# Yay_n_Ders_2.net
KiCad netlist of a schematic drawn in EAGLE
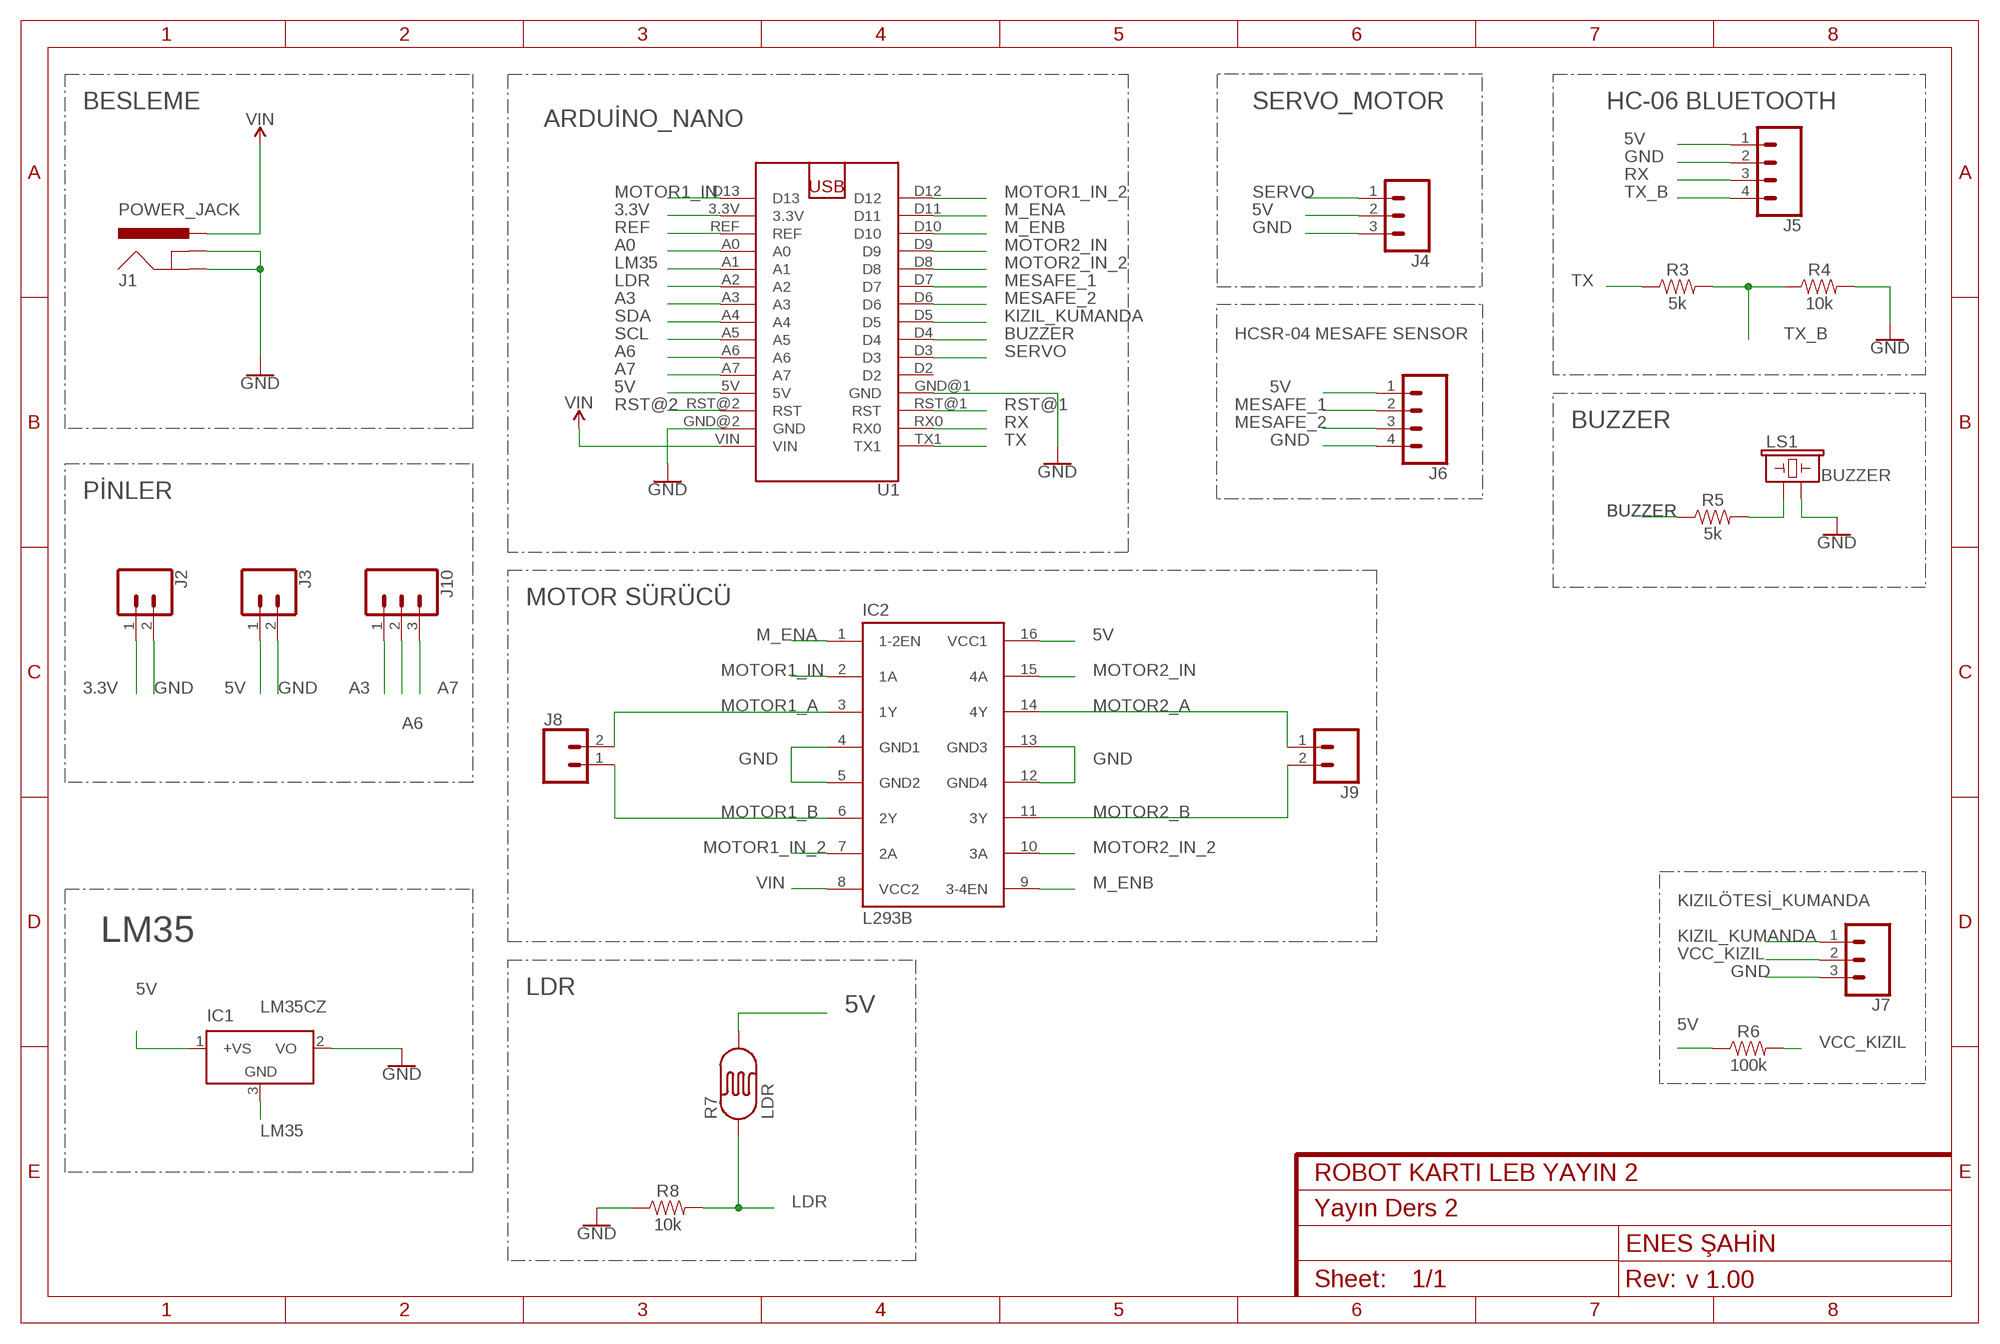
[diagram p0: schematic, sheet 1]

(export (version "E")
  (design (tool "Eeschema 10.0.6"))
  (components
    (comp (ref "IC1")
      (value "LM35CZ")
      (footprint "eagle-import:TO92")
      (libsource (lib "eagle-import") (part "LM35CZ"))
    )
    (comp (ref "IC2")
      (value "L293B")
      (footprint "eagle-import:DIL16")
      (fields (field (name "MPN") "L293D"))
      (libsource (lib "eagle-import") (part "L293D"))
    )
    (comp (ref "J1")
      (value "POWER_JACK")
      (footprint "eagle-import:POWER_JACK_PTH")
      (libsource (lib "eagle-import") (part "POWER_JACK"))
    )
    (comp (ref "J2")
      (value "CONN_02")
      (footprint "eagle-import:1X02")
      (libsource (lib "eagle-import") (part "CONN_02"))
    )
    (comp (ref "J3")
      (value "CONN_02")
      (footprint "eagle-import:1X02")
      (libsource (lib "eagle-import") (part "CONN_02"))
    )
    (comp (ref "J4")
      (value "CONN_03")
      (footprint "eagle-import:1X03")
      (libsource (lib "eagle-import") (part "CONN_03"))
    )
    (comp (ref "J5")
      (value "CONN_04")
      (footprint "eagle-import:1X04")
      (libsource (lib "eagle-import") (part "CONN_04"))
    )
    (comp (ref "J6")
      (value "CONN_04")
      (footprint "eagle-import:1X04")
      (libsource (lib "eagle-import") (part "CONN_04"))
    )
    (comp (ref "J7")
      (value "CONN_03")
      (footprint "eagle-import:1X03")
      (libsource (lib "eagle-import") (part "CONN_03"))
    )
    (comp (ref "J8")
      (value "CONN_02")
      (footprint "eagle-import:1X02")
      (libsource (lib "eagle-import") (part "CONN_02"))
    )
    (comp (ref "J9")
      (value "CONN_02")
      (footprint "eagle-import:1X02")
      (libsource (lib "eagle-import") (part "CONN_02"))
    )
    (comp (ref "J10")
      (value "CONN_03")
      (footprint "eagle-import:1X03")
      (libsource (lib "eagle-import") (part "CONN_03"))
    )
    (comp (ref "LS1")
      (value "BUZZER")
      (footprint "eagle-import:BUZZER-12MM")
      (libsource (lib "eagle-import") (part "BUZZER-PTH"))
    )
    (comp (ref "R3")
      (value "5k")
      (footprint "eagle-import:AXIAL-0.3")
      (libsource (lib "eagle-import") (part "SparkFun-Resistors_532_1KOHM-HORIZ-1/4W-1%"))
    )
    (comp (ref "R4")
      (value "10k")
      (footprint "eagle-import:AXIAL-0.3")
      (libsource (lib "eagle-import") (part "SparkFun-Resistors_532_1KOHM-HORIZ-1/4W-1%"))
    )
    (comp (ref "R5")
      (value "5k")
      (footprint "eagle-import:AXIAL-0.3")
      (libsource (lib "eagle-import") (part "SparkFun-Resistors_532_1KOHM-HORIZ-1/4W-1%"))
    )
    (comp (ref "R6")
      (value "100k")
      (footprint "eagle-import:AXIAL-0.3")
      (libsource (lib "eagle-import") (part "1KOHM-HORIZ-1/4W-1%"))
    )
    (comp (ref "R7")
      (value "LDR")
      (footprint "eagle-import:PHOTOCELL")
      (libsource (lib "eagle-import") (part "PHOTOCELLPTH"))
    )
    (comp (ref "R8")
      (value "10k")
      (footprint "eagle-import:AXIAL-0.3")
      (libsource (lib "eagle-import") (part "1KOHM-HORIZ-1/4W-1%"))
    )
    (comp (ref "U1")
      (value "ARDUINO_NANO")
      (footprint "eagle-import:ARDUINO_NANO")
      (libsource (lib "eagle-import") (part "ARDUINO_NANO"))
    )
  )
  (nets
    (net (code "1") (name "/3.3V") (class "Default")
      (node (ref "J2") (pin "1") (pinfunction "1_1") (pintype "passive"))
      (node (ref "U1") (pin "3.3V") (pinfunction "3.3V_3.3V") (pintype "bidirectional"))
    )
    (net (code "2") (name "/5V") (class "Default")
      (node (ref "IC1") (pin "1") (pinfunction "+VS_1") (pintype "input"))
      (node (ref "IC2") (pin "16") (pinfunction "VCC1_16") (pintype "power_in"))
      (node (ref "J3") (pin "1") (pinfunction "1_1") (pintype "passive"))
      (node (ref "J4") (pin "2") (pinfunction "2_2") (pintype "passive"))
      (node (ref "J5") (pin "1") (pinfunction "1_1") (pintype "passive"))
      (node (ref "J6") (pin "1") (pinfunction "1_1") (pintype "passive"))
      (node (ref "R6") (pin "P$1") (pinfunction "1_P$1") (pintype "passive"))
      (node (ref "R7") (pin "2") (pinfunction "P$2_2") (pintype "bidirectional"))
      (node (ref "U1") (pin "5V") (pinfunction "5V_5V") (pintype "bidirectional"))
    )
    (net (code "3") (name "/A0") (class "Default")
      (node (ref "U1") (pin "A0") (pinfunction "A0_A0") (pintype "bidirectional"))
    )
    (net (code "4") (name "/A3") (class "Default")
      (node (ref "J10") (pin "1") (pinfunction "1_1") (pintype "passive"))
      (node (ref "U1") (pin "A3") (pinfunction "A3_A3") (pintype "bidirectional"))
    )
    (net (code "5") (name "/A6") (class "Default")
      (node (ref "J10") (pin "2") (pinfunction "2_2") (pintype "passive"))
      (node (ref "U1") (pin "A6") (pinfunction "A6_A6") (pintype "bidirectional"))
    )
    (net (code "6") (name "/A7") (class "Default")
      (node (ref "J10") (pin "3") (pinfunction "3_3") (pintype "passive"))
      (node (ref "U1") (pin "A7") (pinfunction "A7_A7") (pintype "bidirectional"))
    )
    (net (code "7") (name "/BUZZER") (class "Default")
      (node (ref "R5") (pin "P$1") (pinfunction "1_P$1") (pintype "passive"))
      (node (ref "U1") (pin "D4") (pinfunction "D4_D4") (pintype "bidirectional"))
    )
    (net (code "8") (name "/KIZIL_KUMANDA") (class "Default")
      (node (ref "J7") (pin "1") (pinfunction "1_1") (pintype "passive"))
      (node (ref "U1") (pin "D5") (pinfunction "D5_D5") (pintype "bidirectional"))
    )
    (net (code "9") (name "/LDR") (class "Default")
      (node (ref "R7") (pin "1") (pinfunction "P$1_1") (pintype "bidirectional"))
      (node (ref "R8") (pin "P$2") (pinfunction "2_P$2") (pintype "passive"))
      (node (ref "U1") (pin "A2") (pinfunction "A2_A2") (pintype "bidirectional"))
    )
    (net (code "10") (name "/LM35") (class "Default")
      (node (ref "IC1") (pin "3") (pinfunction "GND_3") (pintype "power_in"))
      (node (ref "U1") (pin "A1") (pinfunction "A1_A1") (pintype "bidirectional"))
    )
    (net (code "11") (name "/MESAFE_1") (class "Default")
      (node (ref "J6") (pin "2") (pinfunction "2_2") (pintype "passive"))
      (node (ref "U1") (pin "D7") (pinfunction "D7_D7") (pintype "bidirectional"))
    )
    (net (code "12") (name "/MESAFE_2") (class "Default")
      (node (ref "J6") (pin "3") (pinfunction "3_3") (pintype "passive"))
      (node (ref "U1") (pin "D6") (pinfunction "D6_D6") (pintype "bidirectional"))
    )
    (net (code "13") (name "/MOTOR1_A") (class "Default")
      (node (ref "IC2") (pin "3") (pinfunction "1Y_3") (pintype "output"))
      (node (ref "J8") (pin "2") (pinfunction "2_2") (pintype "passive"))
    )
    (net (code "14") (name "/MOTOR1_B") (class "Default")
      (node (ref "IC2") (pin "6") (pinfunction "2Y_6") (pintype "output"))
      (node (ref "J8") (pin "1") (pinfunction "1_1") (pintype "passive"))
    )
    (net (code "15") (name "/MOTOR1_IN") (class "Default")
      (node (ref "IC2") (pin "2") (pinfunction "1A_2") (pintype "input"))
      (node (ref "U1") (pin "D13") (pinfunction "D13_D13") (pintype "bidirectional"))
    )
    (net (code "16") (name "/MOTOR1_IN_2") (class "Default")
      (node (ref "IC2") (pin "7") (pinfunction "2A_7") (pintype "input"))
      (node (ref "U1") (pin "D12") (pinfunction "D12_D12") (pintype "bidirectional"))
    )
    (net (code "17") (name "/MOTOR2_A") (class "Default")
      (node (ref "IC2") (pin "14") (pinfunction "4Y_14") (pintype "output"))
      (node (ref "J9") (pin "1") (pinfunction "1_1") (pintype "passive"))
    )
    (net (code "18") (name "/MOTOR2_B") (class "Default")
      (node (ref "IC2") (pin "11") (pinfunction "3Y_11") (pintype "output"))
      (node (ref "J9") (pin "2") (pinfunction "2_2") (pintype "passive"))
    )
    (net (code "19") (name "/MOTOR2_IN") (class "Default")
      (node (ref "IC2") (pin "15") (pinfunction "4A_15") (pintype "input"))
      (node (ref "U1") (pin "D9") (pinfunction "D9_D9") (pintype "bidirectional"))
    )
    (net (code "20") (name "/MOTOR2_IN_2") (class "Default")
      (node (ref "IC2") (pin "10") (pinfunction "3A_10") (pintype "input"))
      (node (ref "U1") (pin "D8") (pinfunction "D8_D8") (pintype "bidirectional"))
    )
    (net (code "21") (name "/M_ENA") (class "Default")
      (node (ref "IC2") (pin "1") (pinfunction "1-2EN_1") (pintype "input"))
      (node (ref "U1") (pin "D11") (pinfunction "D11_D11") (pintype "bidirectional"))
    )
    (net (code "22") (name "/M_ENB") (class "Default")
      (node (ref "IC2") (pin "9") (pinfunction "3-4EN_9") (pintype "input"))
      (node (ref "U1") (pin "D10") (pinfunction "D10_D10") (pintype "bidirectional"))
    )
    (net (code "23") (name "/REF") (class "Default")
      (node (ref "U1") (pin "REF") (pinfunction "REF_REF") (pintype "bidirectional"))
    )
    (net (code "24") (name "/RST@1") (class "Default")
      (node (ref "U1") (pin "RST@1") (pinfunction "RST_RST@1") (pintype "bidirectional"))
    )
    (net (code "25") (name "/RST@2") (class "Default")
      (node (ref "U1") (pin "RST@2") (pinfunction "RST_RST@2") (pintype "bidirectional"))
    )
    (net (code "26") (name "/RX") (class "Default")
      (node (ref "J5") (pin "3") (pinfunction "3_3") (pintype "passive"))
      (node (ref "U1") (pin "RX0") (pinfunction "RX0_RX0") (pintype "bidirectional"))
    )
    (net (code "27") (name "/SCL") (class "Default")
      (node (ref "U1") (pin "A5") (pinfunction "A5_A5") (pintype "bidirectional"))
    )
    (net (code "28") (name "/SDA") (class "Default")
      (node (ref "U1") (pin "A4") (pinfunction "A4_A4") (pintype "bidirectional"))
    )
    (net (code "29") (name "/SERVO") (class "Default")
      (node (ref "J4") (pin "1") (pinfunction "1_1") (pintype "passive"))
      (node (ref "U1") (pin "D3") (pinfunction "D3_D3") (pintype "bidirectional"))
    )
    (net (code "30") (name "/TX") (class "Default")
      (node (ref "R3") (pin "P$1") (pinfunction "1_P$1") (pintype "passive"))
      (node (ref "U1") (pin "TX1") (pinfunction "TX1_TX1") (pintype "bidirectional"))
    )
    (net (code "31") (name "/TX_B") (class "Default")
      (node (ref "J5") (pin "4") (pinfunction "4_4") (pintype "passive"))
      (node (ref "R3") (pin "P$2") (pinfunction "2_P$2") (pintype "passive"))
      (node (ref "R4") (pin "P$1") (pinfunction "1_P$1") (pintype "passive"))
    )
    (net (code "32") (name "/VCC_KIZIL") (class "Default")
      (node (ref "J7") (pin "2") (pinfunction "2_2") (pintype "passive"))
      (node (ref "R6") (pin "P$2") (pinfunction "2_P$2") (pintype "passive"))
    )
    (net (code "33") (name "GND") (class "Default")
      (node (ref "IC1") (pin "2") (pinfunction "VO_2") (pintype "input"))
      (node (ref "IC2") (pin "12") (pinfunction "GND4_12") (pintype "power_in"))
      (node (ref "IC2") (pin "13") (pinfunction "GND3_13") (pintype "power_in"))
      (node (ref "IC2") (pin "4") (pinfunction "GND1_4") (pintype "power_in"))
      (node (ref "IC2") (pin "5") (pinfunction "GND2_5") (pintype "power_in"))
      (node (ref "J1") (pin "GND") (pinfunction "GND_GND") (pintype "bidirectional"))
      (node (ref "J1") (pin "GNDBREAK") (pinfunction "GNDBREAK_GNDBREAK") (pintype "bidirectional"))
      (node (ref "J2") (pin "2") (pinfunction "2_2") (pintype "passive"))
      (node (ref "J3") (pin "2") (pinfunction "2_2") (pintype "passive"))
      (node (ref "J4") (pin "3") (pinfunction "3_3") (pintype "passive"))
      (node (ref "J5") (pin "2") (pinfunction "2_2") (pintype "passive"))
      (node (ref "J6") (pin "4") (pinfunction "4_4") (pintype "passive"))
      (node (ref "J7") (pin "3") (pinfunction "3_3") (pintype "passive"))
      (node (ref "LS1") (pin "-") (pinfunction "2_-") (pintype "passive"))
      (node (ref "R4") (pin "P$2") (pinfunction "2_P$2") (pintype "passive"))
      (node (ref "R8") (pin "P$1") (pinfunction "1_P$1") (pintype "passive"))
      (node (ref "U1") (pin "GND@1") (pinfunction "GND_GND@1") (pintype "bidirectional"))
      (node (ref "U1") (pin "GND@2") (pinfunction "GND_GND@2") (pintype "bidirectional"))
    )
    (net (code "34") (name "Net-(LS1-1)") (class "Default")
      (node (ref "LS1") (pin "+") (pinfunction "1_+") (pintype "passive"))
      (node (ref "R5") (pin "P$2") (pinfunction "2_P$2") (pintype "passive"))
    )
    (net (code "35") (name "VIN") (class "Default")
      (node (ref "IC2") (pin "8") (pinfunction "VCC2_8") (pintype "power_in"))
      (node (ref "J1") (pin "PWR") (pinfunction "PWR_PWR") (pintype "bidirectional"))
      (node (ref "U1") (pin "VIN") (pinfunction "VIN_VIN") (pintype "bidirectional"))
    )
    (net (code "36") (name "unconnected-(U1-PadD2)") (class "Default")
      (node (ref "U1") (pin "D2") (pinfunction "D2_D2") (pintype "bidirectional"))
    )
  )
)
